# S7CAS-PLEIADES-CARTE-MERE_Pxx_MOTEUR.net
KiCad netlist of a schematic drawn in Altium Designer
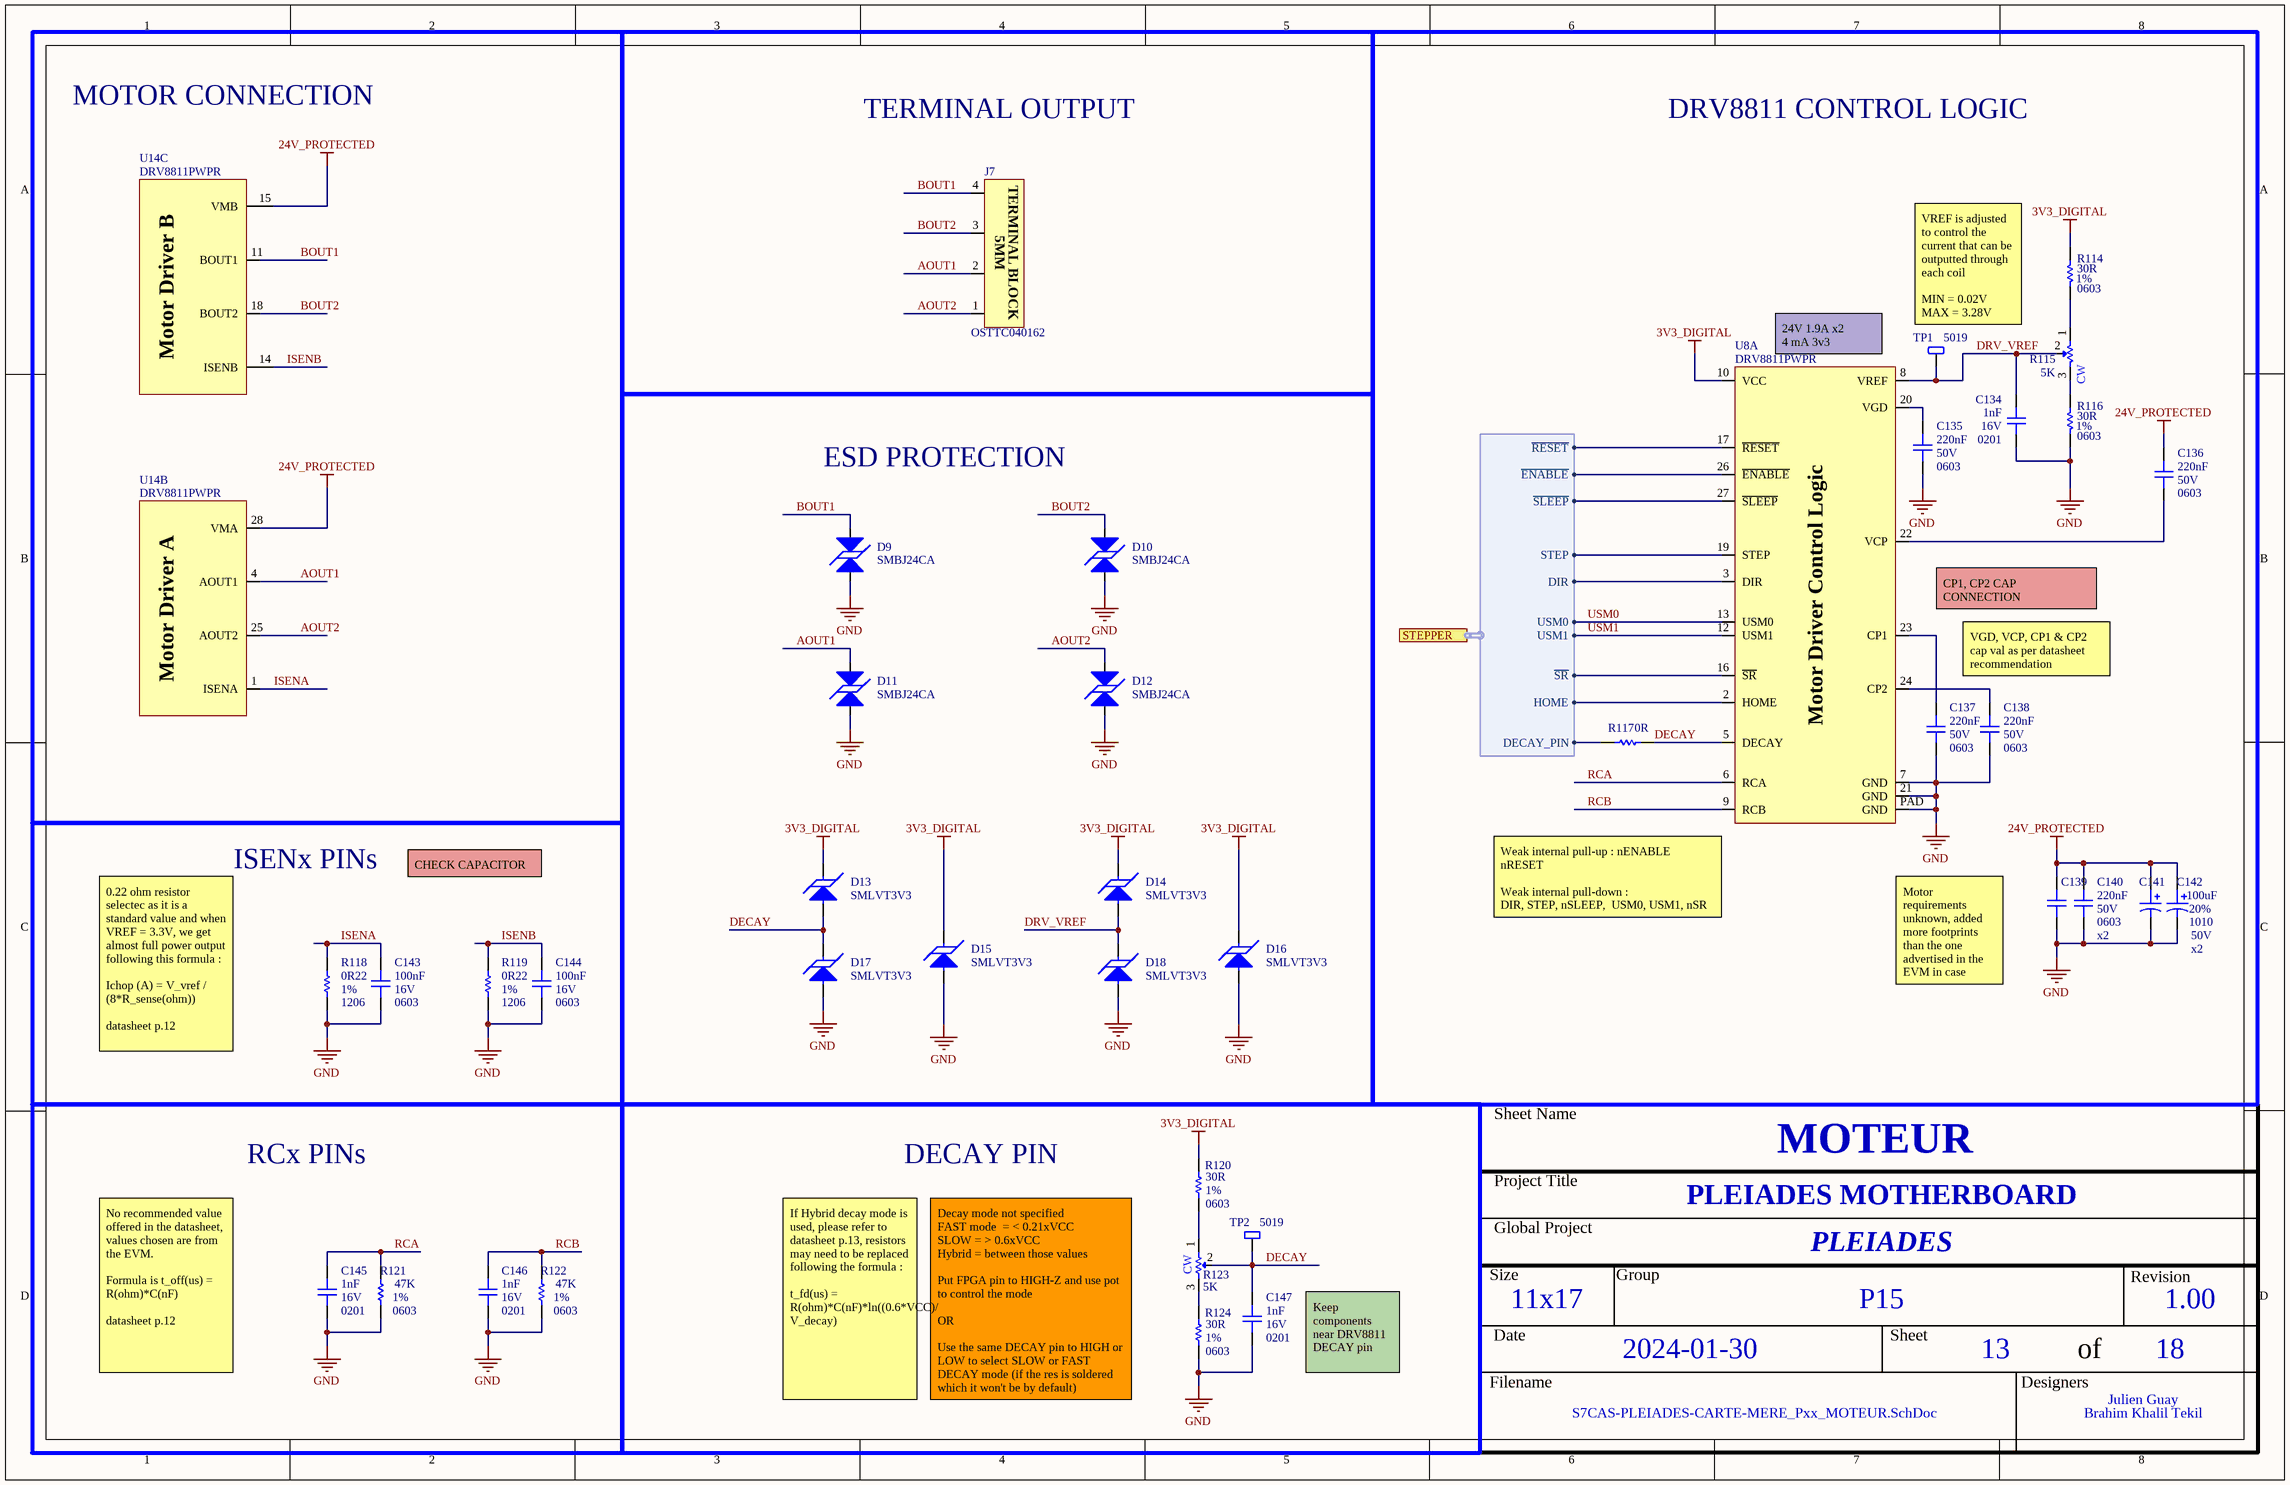
[diagram p0: S7CAS-PLEIADES-CARTE-MERE_Pxx_MOTEUR.SchDoc]

(export (version "E")
  (design (tool "Eeschema 10.0.6"))
  (components
    (comp (ref "C134")
      (value "1nF")
      (footprint "CAP_0201")
      (description "CAP - 0201")
      (fields
        (field (name "VOLTAGE") "16V")
        (field (name "PACKAGE") "0201")
        (field (name "CREATEDBY") "Jonathan Bouchard")
      )
      (libsource (lib "S7CAS_LIB2023") (part "CAP - 0201"))
    )
    (comp (ref "C135")
      (value "220nF")
      (footprint "CAP_0603")
      (description "CAP - 0603")
      (fields
        (field (name "VOLTAGE") "50V")
        (field (name "PACKAGE") "0603")
        (field (name "CREATEDBY") "Jonathan Bouchard")
      )
      (libsource (lib "S7CAS_LIB2023") (part "CAP - 0603"))
    )
    (comp (ref "C136")
      (value "220nF")
      (footprint "CAP_0603")
      (description "CAP - 0603")
      (fields
        (field (name "VOLTAGE") "50V")
        (field (name "PACKAGE") "0603")
        (field (name "CREATEDBY") "Jonathan Bouchard")
      )
      (libsource (lib "S7CAS_LIB2023") (part "CAP - 0603"))
    )
    (comp (ref "C137")
      (value "220nF")
      (footprint "CAP_0603")
      (description "CAP - 0603")
      (fields
        (field (name "VOLTAGE") "50V")
        (field (name "PACKAGE") "0603")
        (field (name "CREATEDBY") "Jonathan Bouchard")
      )
      (libsource (lib "S7CAS_LIB2023") (part "CAP - 0603"))
    )
    (comp (ref "C138")
      (value "220nF")
      (footprint "CAP_0603")
      (description "CAP - 0603")
      (fields
        (field (name "VOLTAGE") "50V")
        (field (name "PACKAGE") "0603")
        (field (name "CREATEDBY") "Jonathan Bouchard")
      )
      (libsource (lib "S7CAS_LIB2023") (part "CAP - 0603"))
    )
    (comp (ref "C139")
      (value "CAP - 0603")
      (footprint "CAP_0603")
      (fields (field (name "VOLTAGE") "50V") (field (name "CREATEDBY") "Jonathan Bouchard"))
      (libsource (lib "S7CAS_LIB2023") (part "CAP - 0603"))
    )
    (comp (ref "C140")
      (value "220nF")
      (footprint "CAP_0603")
      (description "CAP - 0603")
      (fields
        (field (name "VOLTAGE") "50V")
        (field (name "PACKAGE") "0603")
        (field (name "CREATEDBY") "Jonathan Bouchard")
      )
      (libsource (lib "S7CAS_LIB2023") (part "CAP - 0603"))
    )
    (comp (ref "C141")
      (value "MAL215099101E3")
      (footprint "CAP_ALU_1010_vishay")
      (description "CAP - ALU 100uF 20% 50V - 1010")
      (fields
        (field (name "MFG") "Vishay Dale")
        (field (name "VOLTAGE") "50V")
        (field (name "CREATEDBY") "Jonathan Bouchard")
      )
      (libsource (lib "S7CAS_LIB2023") (part "CAP_ALU_MAL215099101E3"))
    )
    (comp (ref "C142")
      (value "100uF")
      (footprint "CAP_ALU_1010_vishay")
      (description "CAP - ALU 100uF 20% 50V - 1010")
      (fields
        (field (name "MFG") "Vishay Dale")
        (field (name "MFG PART NUMBER") "MAL215099101E3")
        (field (name "VOLTAGE") "50V")
        (field (name "PACKAGE") "1010")
        (field (name "PRECISION") "20%")
        (field (name "CREATEDBY") "Jonathan Bouchard")
      )
      (libsource (lib "S7CAS_LIB2023") (part "CAP_ALU_MAL215099101E3"))
    )
    (comp (ref "C143")
      (value "100nF")
      (footprint "CAP_0603")
      (description "CAP - 0603")
      (fields
        (field (name "VOLTAGE") "16V")
        (field (name "PACKAGE") "0603")
        (field (name "CREATEDBY") "Jonathan Bouchard")
      )
      (libsource (lib "S7CAS_LIB2023") (part "CAP - 0603"))
    )
    (comp (ref "C144")
      (value "100nF")
      (footprint "CAP_0603")
      (description "CAP - 0603")
      (fields
        (field (name "VOLTAGE") "16V")
        (field (name "PACKAGE") "0603")
        (field (name "CREATEDBY") "Jonathan Bouchard")
      )
      (libsource (lib "S7CAS_LIB2023") (part "CAP - 0603"))
    )
    (comp (ref "C145")
      (value "1nF")
      (footprint "CAP_0201")
      (description "CAP - 0201")
      (fields
        (field (name "VOLTAGE") "16V")
        (field (name "PACKAGE") "0201")
        (field (name "CREATEDBY") "Jonathan Bouchard")
      )
      (libsource (lib "S7CAS_LIB2023") (part "CAP - 0201"))
    )
    (comp (ref "C146")
      (value "1nF")
      (footprint "CAP_0201")
      (description "CAP - 0201")
      (fields
        (field (name "VOLTAGE") "16V")
        (field (name "PACKAGE") "0201")
        (field (name "CREATEDBY") "Jonathan Bouchard")
      )
      (libsource (lib "S7CAS_LIB2023") (part "CAP - 0201"))
    )
    (comp (ref "C147")
      (value "1nF")
      (footprint "CAP_0201")
      (description "CAP - 0201")
      (fields
        (field (name "VOLTAGE") "16V")
        (field (name "PACKAGE") "0201")
        (field (name "CREATEDBY") "Jonathan Bouchard")
      )
      (libsource (lib "S7CAS_LIB2023") (part "CAP - 0201"))
    )
    (comp (ref "D9")
      (value "SMBJ24CA")
      (footprint "TVS_PWR_SMBJ36CA")
      (description "TVS - 24V 26.7V 600W - DO214AA")
      (fields
        (field (name "CREATEDBY/DATE") "Arnaud Samson - 06/07/18")
        (field (name "VERIFIEDBY") "Jonathan Bouchard - 2018-07-13")
      )
      (libsource (lib "S7CAS_LIB2023") (part "TVS_PWR_SMBJ24CA"))
    )
    (comp (ref "D10")
      (value "SMBJ24CA")
      (footprint "TVS_PWR_SMBJ36CA")
      (description "TVS - 24V 26.7V 600W - DO214AA")
      (fields
        (field (name "CREATEDBY/DATE") "Arnaud Samson - 06/07/18")
        (field (name "VERIFIEDBY") "Jonathan Bouchard - 2018-07-13")
      )
      (libsource (lib "S7CAS_LIB2023") (part "TVS_PWR_SMBJ24CA"))
    )
    (comp (ref "D11")
      (value "SMBJ24CA")
      (footprint "TVS_PWR_SMBJ36CA")
      (description "TVS - 24V 26.7V 600W - DO214AA")
      (fields
        (field (name "CREATEDBY/DATE") "Arnaud Samson - 06/07/18")
        (field (name "VERIFIEDBY") "Jonathan Bouchard - 2018-07-13")
      )
      (libsource (lib "S7CAS_LIB2023") (part "TVS_PWR_SMBJ24CA"))
    )
    (comp (ref "D12")
      (value "SMBJ24CA")
      (footprint "TVS_PWR_SMBJ36CA")
      (description "TVS - 24V 26.7V 600W - DO214AA")
      (fields
        (field (name "CREATEDBY/DATE") "Arnaud Samson - 06/07/18")
        (field (name "VERIFIEDBY") "Jonathan Bouchard - 2018-07-13")
      )
      (libsource (lib "S7CAS_LIB2023") (part "TVS_PWR_SMBJ24CA"))
    )
    (comp (ref "D13")
      (value "SMLVT3V3")
      (footprint "TVS_POW_SMLVT3V3")
      (description "TVS - 3.3V 10.3V 600W - DO214AA")
      (fields
        (field (name "CREATEDBY/DATE") "Jonathan Bouchard - 2019-04-27")
        (field (name "VERIFIEDBY") "Nicolas V. (2019-05-06)")
      )
      (libsource (lib "S7CAS_LIB2023") (part "TVS_POW_SMLVT3V3"))
    )
    (comp (ref "D14")
      (value "SMLVT3V3")
      (footprint "TVS_POW_SMLVT3V3")
      (description "TVS - 3.3V 10.3V 600W - DO214AA")
      (fields
        (field (name "CREATEDBY/DATE") "Jonathan Bouchard - 2019-04-27")
        (field (name "VERIFIEDBY") "Nicolas V. (2019-05-06)")
      )
      (libsource (lib "S7CAS_LIB2023") (part "TVS_POW_SMLVT3V3"))
    )
    (comp (ref "D15")
      (value "SMLVT3V3")
      (footprint "TVS_POW_SMLVT3V3")
      (description "TVS - 3.3V 10.3V 600W - DO214AA")
      (fields
        (field (name "CREATEDBY/DATE") "Jonathan Bouchard - 2019-04-27")
        (field (name "VERIFIEDBY") "Nicolas V. (2019-05-06)")
      )
      (libsource (lib "S7CAS_LIB2023") (part "TVS_POW_SMLVT3V3"))
    )
    (comp (ref "D16")
      (value "SMLVT3V3")
      (footprint "TVS_POW_SMLVT3V3")
      (description "TVS - 3.3V 10.3V 600W - DO214AA")
      (fields
        (field (name "CREATEDBY/DATE") "Jonathan Bouchard - 2019-04-27")
        (field (name "VERIFIEDBY") "Nicolas V. (2019-05-06)")
      )
      (libsource (lib "S7CAS_LIB2023") (part "TVS_POW_SMLVT3V3"))
    )
    (comp (ref "D17")
      (value "SMLVT3V3")
      (footprint "TVS_POW_SMLVT3V3")
      (description "TVS - 3.3V 10.3V 600W - DO214AA")
      (fields
        (field (name "CREATEDBY/DATE") "Jonathan Bouchard - 2019-04-27")
        (field (name "VERIFIEDBY") "Nicolas V. (2019-05-06)")
      )
      (libsource (lib "S7CAS_LIB2023") (part "TVS_POW_SMLVT3V3"))
    )
    (comp (ref "D18")
      (value "SMLVT3V3")
      (footprint "TVS_POW_SMLVT3V3")
      (description "TVS - 3.3V 10.3V 600W - DO214AA")
      (fields
        (field (name "CREATEDBY/DATE") "Jonathan Bouchard - 2019-04-27")
        (field (name "VERIFIEDBY") "Nicolas V. (2019-05-06)")
      )
      (libsource (lib "S7CAS_LIB2023") (part "TVS_POW_SMLVT3V3"))
    )
    (comp (ref "J7")
      (value "OSTTC040162")
      (footprint "CONN_TERMINAL_OSTTA040161")
      (description "CONN -  TERMINAL BLOCK 4POS 5MM - TH")
      (fields (field (name "MFG") "On Shore Technology Inc.") (field (name "CREATEDBY") "Jonathan Bouchard"))
      (libsource (lib "S7CAS_LIB2023") (part "CONN_TERMINAL_OSTTC040162"))
    )
    (comp (ref "R114")
      (value "30R")
      (footprint "RES_0603")
      (description "RES - 0603")
      (fields
        (field (name "PACKAGE") "0603")
        (field (name "PRECISION") "1%")
        (field (name "CREATEDBY") "Jonathan Bouchard")
      )
      (libsource (lib "S7CAS_LIB2023") (part "RES - 0603"))
    )
    (comp (ref "R115")
      (value "5K")
      (footprint "POT_J_LEAD_TOP")
      (description "POT - 0.1W, 1/10W Surface Mount Trimmer Potentiometer Cermet 1.0 Turn Top Adjustment")
      (fields (field (name "Comment") "Part Number"))
      (libsource (lib "S7CAS_LIB2023") (part "POT - TOP ADJ"))
    )
    (comp (ref "R116")
      (value "30R")
      (footprint "RES_0603")
      (description "RES - 0603")
      (fields
        (field (name "PACKAGE") "0603")
        (field (name "PRECISION") "1%")
        (field (name "CREATEDBY") "Jonathan Bouchard")
      )
      (libsource (lib "S7CAS_LIB2023") (part "RES - 0603"))
    )
    (comp (ref "R117")
      (value "0R")
      (footprint "RES_0603")
      (description "RES - 0603")
      (fields (field (name "CREATEDBY") "Jonathan Bouchard"))
      (libsource (lib "S7CAS_LIB2023") (part "RES - 0603"))
    )
    (comp (ref "R118")
      (value "0R22")
      (footprint "RES_1206")
      (description "RES - 1206")
      (fields
        (field (name "PACKAGE") "1206")
        (field (name "PRECISION") "1%")
        (field (name "CREATEDBY") "Jonathan Bouchard")
      )
      (libsource (lib "S7CAS_LIB2023") (part "RES - 1206"))
    )
    (comp (ref "R119")
      (value "0R22")
      (footprint "RES_1206")
      (description "RES - 1206")
      (fields
        (field (name "PACKAGE") "1206")
        (field (name "PRECISION") "1%")
        (field (name "CREATEDBY") "Jonathan Bouchard")
      )
      (libsource (lib "S7CAS_LIB2023") (part "RES - 1206"))
    )
    (comp (ref "R120")
      (value "30R")
      (footprint "RES_0603")
      (description "RES - 0603")
      (fields
        (field (name "PACKAGE") "0603")
        (field (name "PRECISION") "1%")
        (field (name "CREATEDBY") "Jonathan Bouchard")
      )
      (libsource (lib "S7CAS_LIB2023") (part "RES - 0603"))
    )
    (comp (ref "R121")
      (value "47K")
      (footprint "RES_0603")
      (description "RES - 0603")
      (fields
        (field (name "PACKAGE") "0603")
        (field (name "PRECISION") "1%")
        (field (name "CREATEDBY") "Jonathan Bouchard")
      )
      (libsource (lib "S7CAS_LIB2023") (part "RES - 0603"))
    )
    (comp (ref "R122")
      (value "47K")
      (footprint "RES_0603")
      (description "RES - 0603")
      (fields
        (field (name "PACKAGE") "0603")
        (field (name "PRECISION") "1%")
        (field (name "CREATEDBY") "Jonathan Bouchard")
      )
      (libsource (lib "S7CAS_LIB2023") (part "RES - 0603"))
    )
    (comp (ref "R123")
      (value "5K")
      (footprint "POT_J_LEAD_TOP")
      (description "POT - 0.1W, 1/10W Surface Mount Trimmer Potentiometer Cermet 1.0 Turn Top Adjustment")
      (fields (field (name "Comment") "Part Number"))
      (libsource (lib "S7CAS_LIB2023") (part "POT - TOP ADJ"))
    )
    (comp (ref "R124")
      (value "30R")
      (footprint "RES_0603")
      (description "RES - 0603")
      (fields
        (field (name "PACKAGE") "0603")
        (field (name "PRECISION") "1%")
        (field (name "CREATEDBY") "Jonathan Bouchard")
      )
      (libsource (lib "S7CAS_LIB2023") (part "RES - 0603"))
    )
    (comp (ref "TP1")
      (value "5019")
      (footprint "TPO_SMD_5019")
      (description "TPO - PC TEST POINT MINI - SMD")
      (fields
        (field (name "CREATEDBY/DATE") "Olivier Bernard / 5/12/2017")
        (field (name "VERIFIEDBY") "Caroline Paulin / 5 juillet 2018")
      )
      (libsource (lib "S7CAS_LIB2023") (part "TPO_SMD_5019"))
    )
    (comp (ref "TP2")
      (value "5019")
      (footprint "TPO_SMD_5019")
      (description "TPO - PC TEST POINT MINI - SMD")
      (fields
        (field (name "CREATEDBY/DATE") "Olivier Bernard / 5/12/2017")
        (field (name "VERIFIEDBY") "Caroline Paulin / 5 juillet 2018")
      )
      (libsource (lib "S7CAS_LIB2023") (part "TPO_SMD_5019"))
    )
    (comp (ref "U8")
      (value "DRV8811PWPR")
      (footprint "POW_MOTOR_DRV8811PWPR")
      (description "POW - STEPPER MOTOR DRIVER - SOP-28")
      (fields
        (field (name "VOLTAGE") "3 V ~ 5.5 V / 8 V ~ 38 V")
        (field (name "MFG") "Texas Instrument")
        (field (name "CREATEDBY") "Jonathan Bouchard")
      )
      (libsource (lib "S7CAS_LIB2023") (part "POW_MOTOR_DRV8811PWPR"))
    )
    (comp (ref "U14")
      (value "DRV8811PWPR")
      (footprint "POW_MOTOR_DRV8811PWPR")
      (description "POW - STEPPER MOTOR DRIVER - SOP-28")
      (fields
        (field (name "VOLTAGE") "3 V ~ 5.5 V / 8 V ~ 38 V")
        (field (name "MFG") "Texas Instrument")
        (field (name "CREATEDBY") "Jonathan Bouchard")
      )
      (libsource (lib "S7CAS_LIB2023") (part "POW_MOTOR_DRV8811PWPR"))
    )
  )
  (nets
    (net (code "2") (name "/AOUT1") (class "Default")
      (node (ref "D11") (pin "1") (pinfunction "1_1") (pintype "passive"))
      (node (ref "J7") (pin "2") (pinfunction "2_2") (pintype "passive"))
      (node (ref "U14") (pin "4") (pinfunction "AOUT1_4") (pintype "passive"))
    )
    (net (code "3") (name "/AOUT2") (class "Default")
      (node (ref "D12") (pin "1") (pinfunction "1_1") (pintype "passive"))
      (node (ref "J7") (pin "1") (pinfunction "1_1") (pintype "passive"))
      (node (ref "U14") (pin "25") (pinfunction "AOUT2_25") (pintype "passive"))
    )
    (net (code "4") (name "/BOUT1") (class "Default")
      (node (ref "D9") (pin "1") (pinfunction "1_1") (pintype "passive"))
      (node (ref "J7") (pin "4") (pinfunction "4_4") (pintype "passive"))
      (node (ref "U14") (pin "11") (pinfunction "BOUT1_11") (pintype "passive"))
    )
    (net (code "5") (name "/BOUT2") (class "Default")
      (node (ref "D10") (pin "1") (pinfunction "1_1") (pintype "passive"))
      (node (ref "J7") (pin "3") (pinfunction "3_3") (pintype "passive"))
      (node (ref "U14") (pin "18") (pinfunction "BOUT2_18") (pintype "passive"))
    )
    (net (code "6") (name "/DECAY") (class "Default")
      (node (ref "C147") (pin "2") (pinfunction "2_2") (pintype "passive"))
      (node (ref "D13") (pin "A") (pinfunction "A_A") (pintype "passive"))
      (node (ref "D17") (pin "K") (pinfunction "K_K") (pintype "passive"))
      (node (ref "R117") (pin "1") (pinfunction "1_1") (pintype "passive"))
      (node (ref "R123") (pin "2") (pinfunction "2_2") (pintype "passive"))
      (node (ref "TP2") (pin "1") (pinfunction "1_1") (pintype "passive"))
      (node (ref "U8") (pin "5") (pinfunction "DECAY_5") (pintype "passive"))
    )
    (net (code "7") (name "/DECAY_PIN") (class "Default")
      (node (ref "R117") (pin "2") (pinfunction "2_2") (pintype "passive"))
    )
    (net (code "8") (name "/DIR") (class "Default")
      (node (ref "U8") (pin "3") (pinfunction "DIR_3") (pintype "passive"))
    )
    (net (code "9") (name "/DRV_VREF") (class "Default")
      (node (ref "C134") (pin "2") (pinfunction "2_2") (pintype "passive"))
      (node (ref "D14") (pin "A") (pinfunction "A_A") (pintype "passive"))
      (node (ref "D18") (pin "K") (pinfunction "K_K") (pintype "passive"))
      (node (ref "R115") (pin "2") (pinfunction "2_2") (pintype "passive"))
      (node (ref "TP1") (pin "1") (pinfunction "1_1") (pintype "passive"))
      (node (ref "U8") (pin "8") (pinfunction "VREF_8") (pintype "passive"))
    )
    (net (code "10") (name "/HOME") (class "Default")
      (node (ref "U8") (pin "2") (pinfunction "HOME_2") (pintype "passive"))
    )
    (net (code "11") (name "/ISENA") (class "Default")
      (node (ref "C143") (pin "2") (pinfunction "2_2") (pintype "passive"))
      (node (ref "R118") (pin "2") (pinfunction "2_2") (pintype "passive"))
      (node (ref "U14") (pin "1") (pinfunction "ISENA_1") (pintype "passive"))
    )
    (net (code "12") (name "/ISENB") (class "Default")
      (node (ref "C144") (pin "2") (pinfunction "2_2") (pintype "passive"))
      (node (ref "R119") (pin "2") (pinfunction "2_2") (pintype "passive"))
      (node (ref "U14") (pin "14") (pinfunction "ISENB_14") (pintype "passive"))
    )
    (net (code "13") (name "/RCA") (class "Default")
      (node (ref "C145") (pin "2") (pinfunction "2_2") (pintype "passive"))
      (node (ref "R121") (pin "2") (pinfunction "2_2") (pintype "passive"))
      (node (ref "U8") (pin "6") (pinfunction "RCA_6") (pintype "passive"))
    )
    (net (code "14") (name "/RCB") (class "Default")
      (node (ref "C146") (pin "2") (pinfunction "2_2") (pintype "passive"))
      (node (ref "R122") (pin "2") (pinfunction "2_2") (pintype "passive"))
      (node (ref "U8") (pin "9") (pinfunction "RCB_9") (pintype "passive"))
    )
    (net (code "15") (name "/STEP") (class "Default")
      (node (ref "U8") (pin "19") (pinfunction "STEP_19") (pintype "passive"))
    )
    (net (code "16") (name "/USM0") (class "Default")
      (node (ref "U8") (pin "13") (pinfunction "USM0_13") (pintype "passive"))
    )
    (net (code "17") (name "/USM1") (class "Default")
      (node (ref "U8") (pin "12") (pinfunction "USM1_12") (pintype "passive"))
    )
    (net (code "19") (name "/~{ENABLE}") (class "Default")
      (node (ref "U8") (pin "26") (pinfunction "~{ENABLE}_26") (pintype "passive"))
    )
    (net (code "20") (name "/~{RESET}") (class "Default")
      (node (ref "U8") (pin "17") (pinfunction "~{RESET}_17") (pintype "passive"))
    )
    (net (code "21") (name "/~{SLEEP}") (class "Default")
      (node (ref "U8") (pin "27") (pinfunction "~{SLEEP}_27") (pintype "passive"))
    )
    (net (code "22") (name "/~{SR}") (class "Default")
      (node (ref "U8") (pin "16") (pinfunction "~{SR}_16") (pintype "passive"))
    )
    (net (code "23") (name "3V3_DIGITAL") (class "Default")
      (node (ref "D13") (pin "K") (pinfunction "K_K") (pintype "passive"))
      (node (ref "D14") (pin "K") (pinfunction "K_K") (pintype "passive"))
      (node (ref "D15") (pin "K") (pinfunction "K_K") (pintype "passive"))
      (node (ref "D16") (pin "K") (pinfunction "K_K") (pintype "passive"))
      (node (ref "R114") (pin "1") (pinfunction "1_1") (pintype "passive"))
      (node (ref "R120") (pin "1") (pinfunction "1_1") (pintype "passive"))
      (node (ref "U8") (pin "10") (pinfunction "VCC_10") (pintype "passive"))
    )
    (net (code "24") (name "24V_PROTECTED") (class "Default")
      (node (ref "C136") (pin "2") (pinfunction "2_2") (pintype "passive"))
      (node (ref "C139") (pin "2") (pinfunction "2_2") (pintype "passive"))
      (node (ref "C140") (pin "2") (pinfunction "2_2") (pintype "passive"))
      (node (ref "C141") (pin "1") (pinfunction "1_1") (pintype "passive"))
      (node (ref "C142") (pin "1") (pinfunction "1_1") (pintype "passive"))
      (node (ref "U14") (pin "15") (pinfunction "VMB_15") (pintype "passive"))
      (node (ref "U14") (pin "28") (pinfunction "VMA_28") (pintype "passive"))
    )
    (net (code "25") (name "GND") (class "Default")
      (node (ref "C134") (pin "1") (pinfunction "1_1") (pintype "passive"))
      (node (ref "C135") (pin "1") (pinfunction "1_1") (pintype "passive"))
      (node (ref "C137") (pin "1") (pinfunction "1_1") (pintype "passive"))
      (node (ref "C138") (pin "1") (pinfunction "1_1") (pintype "passive"))
      (node (ref "C139") (pin "1") (pinfunction "1_1") (pintype "passive"))
      (node (ref "C140") (pin "1") (pinfunction "1_1") (pintype "passive"))
      (node (ref "C141") (pin "2") (pinfunction "2_2") (pintype "passive"))
      (node (ref "C142") (pin "2") (pinfunction "2_2") (pintype "passive"))
      (node (ref "C143") (pin "1") (pinfunction "1_1") (pintype "passive"))
      (node (ref "C144") (pin "1") (pinfunction "1_1") (pintype "passive"))
      (node (ref "C145") (pin "1") (pinfunction "1_1") (pintype "passive"))
      (node (ref "C146") (pin "1") (pinfunction "1_1") (pintype "passive"))
      (node (ref "C147") (pin "1") (pinfunction "1_1") (pintype "passive"))
      (node (ref "D10") (pin "2") (pinfunction "2_2") (pintype "passive"))
      (node (ref "D11") (pin "2") (pinfunction "2_2") (pintype "passive"))
      (node (ref "D12") (pin "2") (pinfunction "2_2") (pintype "passive"))
      (node (ref "D15") (pin "A") (pinfunction "A_A") (pintype "passive"))
      (node (ref "D16") (pin "A") (pinfunction "A_A") (pintype "passive"))
      (node (ref "D17") (pin "A") (pinfunction "A_A") (pintype "passive"))
      (node (ref "D18") (pin "A") (pinfunction "A_A") (pintype "passive"))
      (node (ref "D9") (pin "2") (pinfunction "2_2") (pintype "passive"))
      (node (ref "R116") (pin "2") (pinfunction "2_2") (pintype "passive"))
      (node (ref "R118") (pin "1") (pinfunction "1_1") (pintype "passive"))
      (node (ref "R119") (pin "1") (pinfunction "1_1") (pintype "passive"))
      (node (ref "R121") (pin "1") (pinfunction "1_1") (pintype "passive"))
      (node (ref "R122") (pin "1") (pinfunction "1_1") (pintype "passive"))
      (node (ref "R124") (pin "2") (pinfunction "2_2") (pintype "passive"))
      (node (ref "U8") (pin "21") (pinfunction "GND_21") (pintype "passive"))
      (node (ref "U8") (pin "7") (pinfunction "GND_7") (pintype "passive"))
      (node (ref "U8") (pin "PAD") (pinfunction "GND_PAD") (pintype "passive"))
    )
    (net (code "26") (name "Net-(R114-Pad2)") (class "Default")
      (node (ref "R114") (pin "2") (pinfunction "2_2") (pintype "passive"))
      (node (ref "R115") (pin "1") (pinfunction "1_1") (pintype "passive"))
    )
    (net (code "27") (name "Net-(R115-Pad3)") (class "Default")
      (node (ref "R115") (pin "3") (pinfunction "3_3") (pintype "passive"))
      (node (ref "R116") (pin "1") (pinfunction "1_1") (pintype "passive"))
    )
    (net (code "28") (name "Net-(R120-Pad2)") (class "Default")
      (node (ref "R120") (pin "2") (pinfunction "2_2") (pintype "passive"))
      (node (ref "R123") (pin "1") (pinfunction "1_1") (pintype "passive"))
    )
    (net (code "29") (name "Net-(R123-Pad3)") (class "Default")
      (node (ref "R123") (pin "3") (pinfunction "3_3") (pintype "passive"))
      (node (ref "R124") (pin "1") (pinfunction "1_1") (pintype "passive"))
    )
    (net (code "30") (name "Net-(U8A-CP1)") (class "Default")
      (node (ref "C137") (pin "2") (pinfunction "2_2") (pintype "passive"))
      (node (ref "U8") (pin "23") (pinfunction "CP1_23") (pintype "passive"))
    )
    (net (code "31") (name "Net-(U8A-CP2)") (class "Default")
      (node (ref "C138") (pin "2") (pinfunction "2_2") (pintype "passive"))
      (node (ref "U8") (pin "24") (pinfunction "CP2_24") (pintype "passive"))
    )
    (net (code "32") (name "Net-(U8A-VCP)") (class "Default")
      (node (ref "C136") (pin "1") (pinfunction "1_1") (pintype "passive"))
      (node (ref "U8") (pin "22") (pinfunction "VCP_22") (pintype "passive"))
    )
    (net (code "33") (name "Net-(U8A-VGD)") (class "Default")
      (node (ref "C135") (pin "2") (pinfunction "2_2") (pintype "passive"))
      (node (ref "U8") (pin "20") (pinfunction "VGD_20") (pintype "passive"))
    )
  )
)
